# 001-0001_Christmas_Ornament_LEDs.net
KiCad netlist of a schematic drawn in Altium Designer
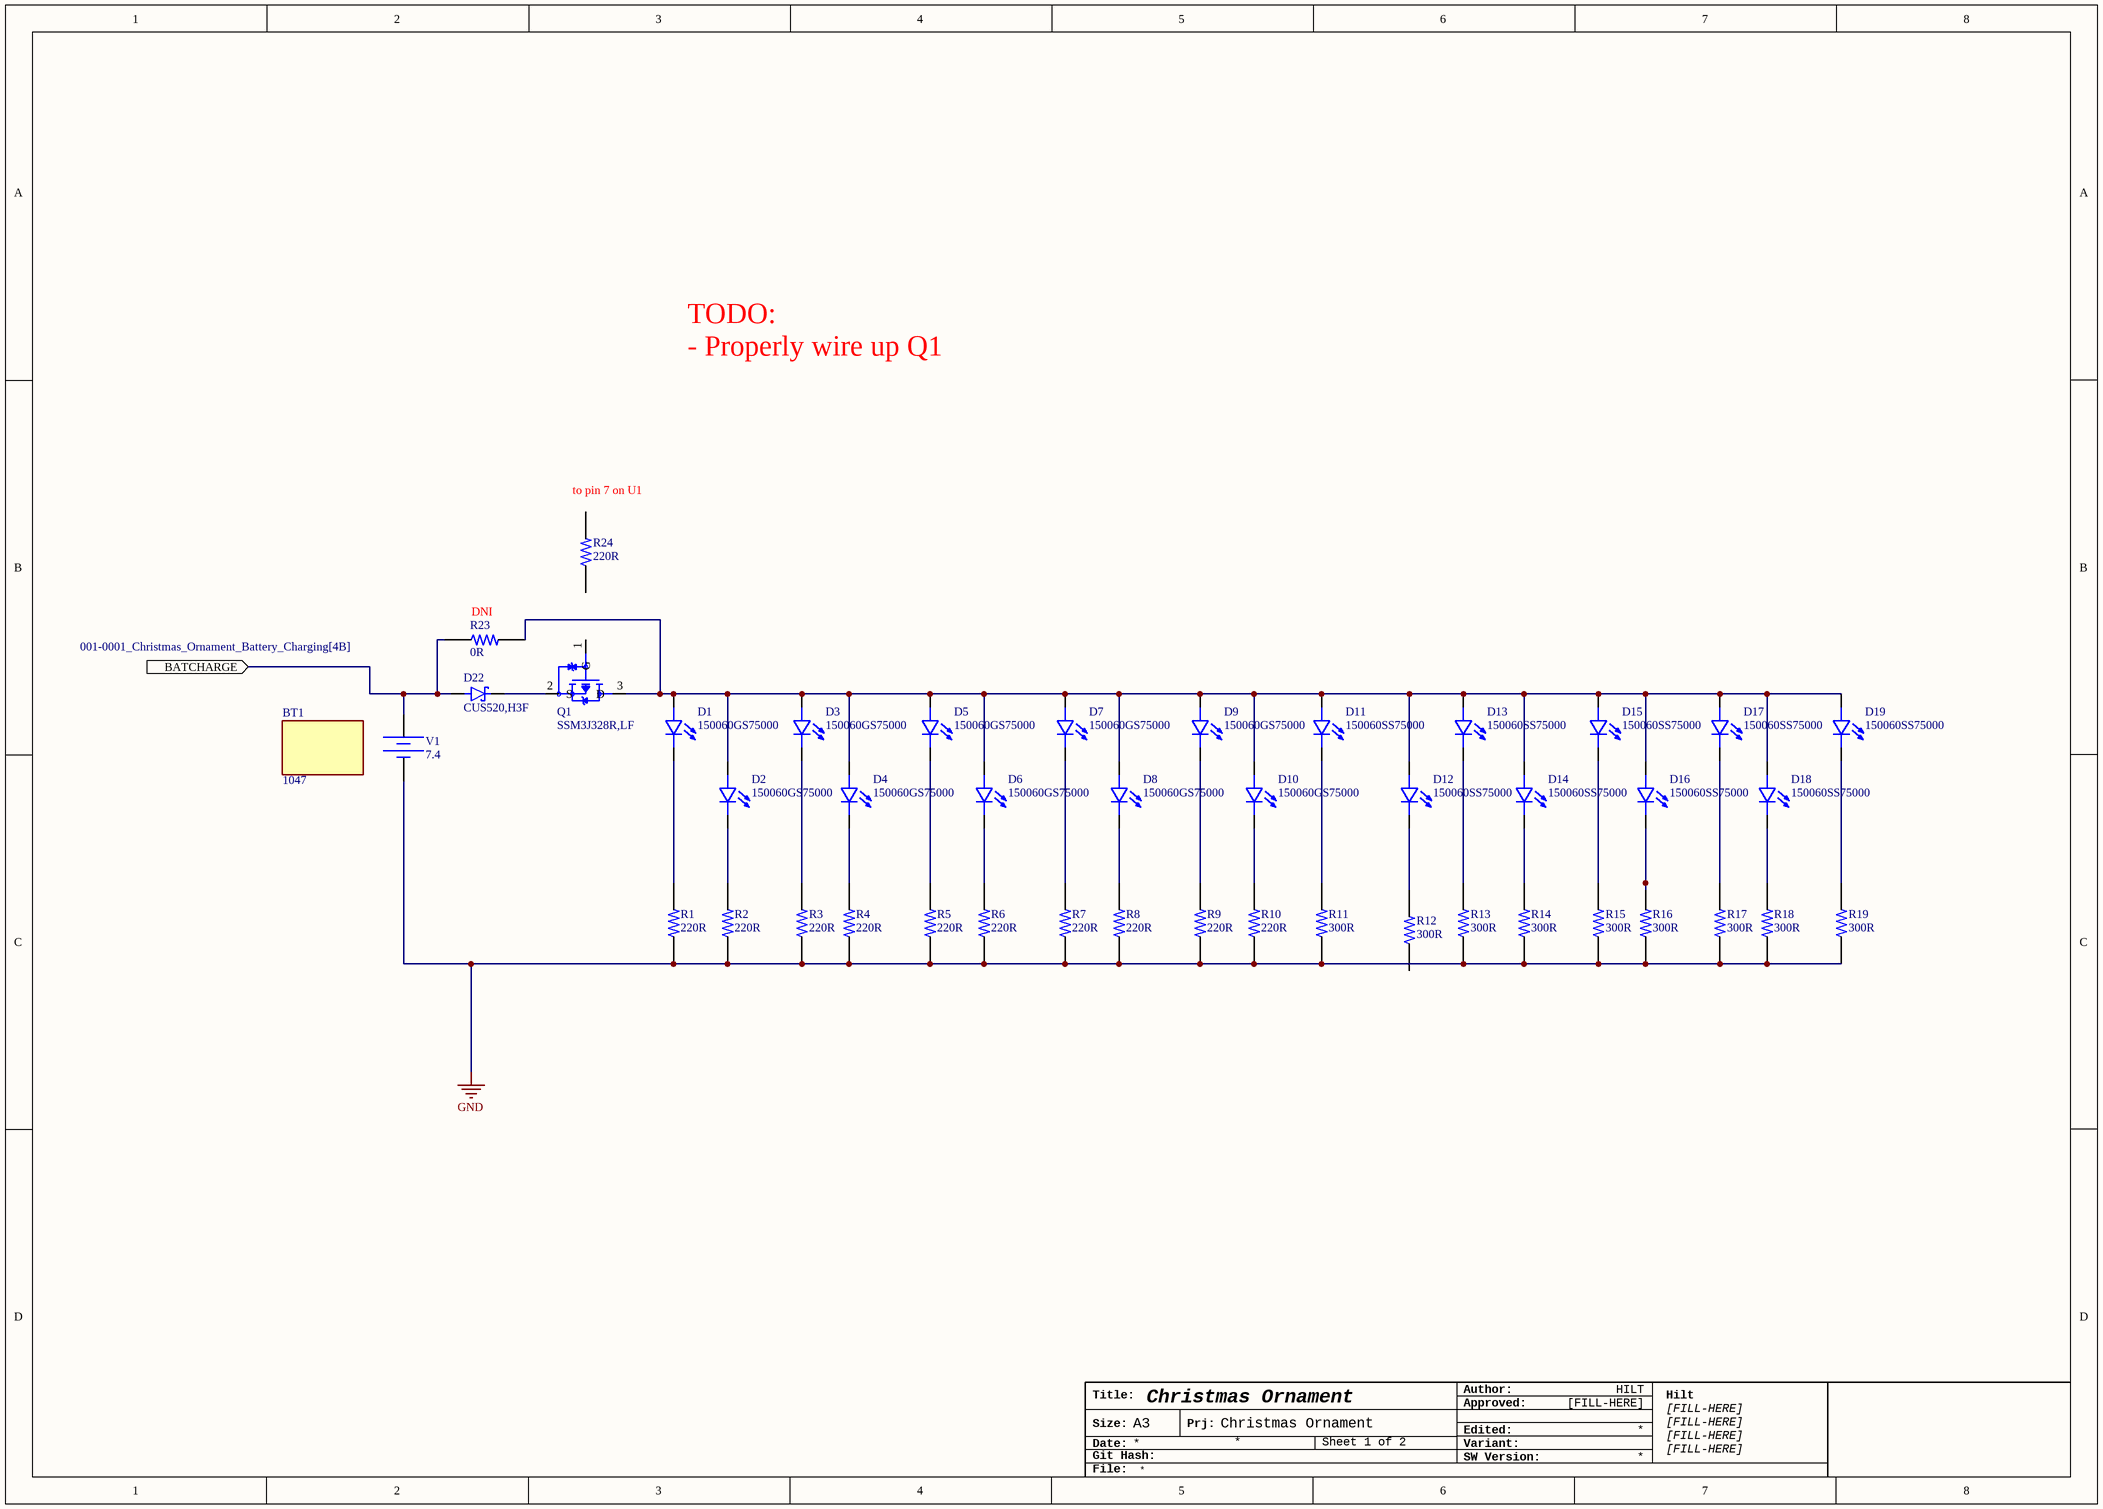
[diagram p0: 001-0001_Christmas_Ornament_LEDs.SchDoc]

(export (version "E")
  (design (tool "Eeschema 10.0.6"))
  (components
    (comp (ref "BT1")
      (value "1047")
      (footprint "BAT_1047")
      (description "18650 Dual Battery Holder")
      (libsource (lib "default") (part "1047"))
    )
    (comp (ref "D1")
      (value "150060GS75000")
      (footprint "LEDC1608X80N")
      (description "Green 520nm LED Indication - Discrete 3.2V 0603 (1608 Metric)")
      (fields (field (name "MF") "Wurth Electronics"))
      (libsource (lib "default") (part "150060GS75000"))
    )
    (comp (ref "D2")
      (value "150060GS75000")
      (footprint "LEDC1608X80N")
      (description "Green 520nm LED Indication - Discrete 3.2V 0603 (1608 Metric)")
      (fields (field (name "MF") "Wurth Electronics"))
      (libsource (lib "default") (part "150060GS75000"))
    )
    (comp (ref "D3")
      (value "150060GS75000")
      (footprint "LEDC1608X80N")
      (description "Green 520nm LED Indication - Discrete 3.2V 0603 (1608 Metric)")
      (fields (field (name "MF") "Wurth Electronics"))
      (libsource (lib "default") (part "150060GS75000"))
    )
    (comp (ref "D4")
      (value "150060GS75000")
      (footprint "LEDC1608X80N")
      (description "Green 520nm LED Indication - Discrete 3.2V 0603 (1608 Metric)")
      (fields (field (name "MF") "Wurth Electronics"))
      (libsource (lib "default") (part "150060GS75000"))
    )
    (comp (ref "D5")
      (value "150060GS75000")
      (footprint "LEDC1608X80N")
      (description "Green 520nm LED Indication - Discrete 3.2V 0603 (1608 Metric)")
      (fields (field (name "MF") "Wurth Electronics"))
      (libsource (lib "default") (part "150060GS75000"))
    )
    (comp (ref "D6")
      (value "150060GS75000")
      (footprint "LEDC1608X80N")
      (description "Green 520nm LED Indication - Discrete 3.2V 0603 (1608 Metric)")
      (fields (field (name "MF") "Wurth Electronics"))
      (libsource (lib "default") (part "150060GS75000"))
    )
    (comp (ref "D7")
      (value "150060GS75000")
      (footprint "LEDC1608X80N")
      (description "Green 520nm LED Indication - Discrete 3.2V 0603 (1608 Metric)")
      (fields (field (name "MF") "Wurth Electronics"))
      (libsource (lib "default") (part "150060GS75000"))
    )
    (comp (ref "D8")
      (value "150060GS75000")
      (footprint "LEDC1608X80N")
      (description "Green 520nm LED Indication - Discrete 3.2V 0603 (1608 Metric)")
      (fields (field (name "MF") "Wurth Electronics"))
      (libsource (lib "default") (part "150060GS75000"))
    )
    (comp (ref "D9")
      (value "150060GS75000")
      (footprint "LEDC1608X80N")
      (description "Green 520nm LED Indication - Discrete 3.2V 0603 (1608 Metric)")
      (fields (field (name "MF") "Wurth Electronics"))
      (libsource (lib "default") (part "150060GS75000"))
    )
    (comp (ref "D10")
      (value "150060GS75000")
      (footprint "LEDC1608X80N")
      (description "Green 520nm LED Indication - Discrete 3.2V 0603 (1608 Metric)")
      (fields (field (name "MF") "Wurth Electronics"))
      (libsource (lib "default") (part "150060GS75000"))
    )
    (comp (ref "D11")
      (value "150060SS75000")
      (footprint "LED_150060SS75000")
      (fields (field (name "MF") "{'manufacturer': u'Wurth Electronics'}"))
      (libsource (lib "default") (part "150060SS75000"))
    )
    (comp (ref "D12")
      (value "150060SS75000")
      (footprint "LED_150060SS75000")
      (fields (field (name "MF") "{'manufacturer': u'Wurth Electronics'}"))
      (libsource (lib "default") (part "150060SS75000"))
    )
    (comp (ref "D13")
      (value "150060SS75000")
      (footprint "LED_150060SS75000")
      (fields (field (name "MF") "{'manufacturer': u'Wurth Electronics'}"))
      (libsource (lib "default") (part "150060SS75000"))
    )
    (comp (ref "D14")
      (value "150060SS75000")
      (footprint "LED_150060SS75000")
      (fields (field (name "MF") "{'manufacturer': u'Wurth Electronics'}"))
      (libsource (lib "default") (part "150060SS75000"))
    )
    (comp (ref "D15")
      (value "150060SS75000")
      (footprint "LED_150060SS75000")
      (fields (field (name "MF") "{'manufacturer': u'Wurth Electronics'}"))
      (libsource (lib "default") (part "150060SS75000"))
    )
    (comp (ref "D16")
      (value "150060SS75000")
      (footprint "LED_150060SS75000")
      (fields (field (name "MF") "{'manufacturer': u'Wurth Electronics'}"))
      (libsource (lib "default") (part "150060SS75000"))
    )
    (comp (ref "D17")
      (value "150060SS75000")
      (footprint "LED_150060SS75000")
      (fields (field (name "MF") "{'manufacturer': u'Wurth Electronics'}"))
      (libsource (lib "default") (part "150060SS75000"))
    )
    (comp (ref "D18")
      (value "150060SS75000")
      (footprint "LED_150060SS75000")
      (fields (field (name "MF") "{'manufacturer': u'Wurth Electronics'}"))
      (libsource (lib "default") (part "150060SS75000"))
    )
    (comp (ref "D19")
      (value "150060SS75000")
      (footprint "LED_150060SS75000")
      (fields (field (name "MF") "{'manufacturer': u'Wurth Electronics'}"))
      (libsource (lib "default") (part "150060SS75000"))
    )
    (comp (ref "D22")
      (value "CUS520,H3F")
      (footprint "CUS520,H3F")
      (description "Diode Schottky 30V 200mA Surface Mount USC")
      (fields (field (name "MF") "Toshiba Semiconductor"))
      (libsource (lib "default") (part "CUS520,H3F"))
    )
    (comp (ref "Q1")
      (value "SSM3J328R,LF")
      (footprint "SSM3J328R,LF")
      (description "P-Channel 20V 6A _Ta_ 1W _Ta_ Surface Mount SOT-23F")
      (fields (field (name "MF") "Toshiba"))
      (libsource (lib "default") (part "SSM3J328R,LF"))
    )
    (comp (ref "R1")
      (value "220R")
      (footprint "default:ERJ-PA3F51R0V")
      (description "RES SMD 220 OHM 1% 1/3W 0603")
      (fields (field (name "MP") "ERJPA3F51R0V"))
      (libsource (lib "default") (part "ERJ-PA3F2200V"))
    )
    (comp (ref "R2")
      (value "220R")
      (footprint "default:ERJ-PA3F51R0V")
      (description "RES SMD 220 OHM 1% 1/3W 0603")
      (fields (field (name "MP") "ERJPA3F51R0V"))
      (libsource (lib "default") (part "ERJ-PA3F2200V"))
    )
    (comp (ref "R3")
      (value "220R")
      (footprint "default:ERJ-PA3F51R0V")
      (description "RES SMD 220 OHM 1% 1/3W 0603")
      (fields (field (name "MP") "ERJPA3F51R0V"))
      (libsource (lib "default") (part "ERJ-PA3F2200V"))
    )
    (comp (ref "R4")
      (value "220R")
      (footprint "default:ERJ-PA3F51R0V")
      (description "RES SMD 220 OHM 1% 1/3W 0603")
      (fields (field (name "MP") "ERJPA3F51R0V"))
      (libsource (lib "default") (part "ERJ-PA3F2200V"))
    )
    (comp (ref "R5")
      (value "220R")
      (footprint "default:ERJ-PA3F51R0V")
      (description "RES SMD 220 OHM 1% 1/3W 0603")
      (fields (field (name "MP") "ERJPA3F51R0V"))
      (libsource (lib "default") (part "ERJ-PA3F2200V"))
    )
    (comp (ref "R6")
      (value "220R")
      (footprint "default:ERJ-PA3F51R0V")
      (description "RES SMD 220 OHM 1% 1/3W 0603")
      (fields (field (name "MP") "ERJPA3F51R0V"))
      (libsource (lib "default") (part "ERJ-PA3F2200V"))
    )
    (comp (ref "R7")
      (value "220R")
      (footprint "default:ERJ-PA3F51R0V")
      (description "RES SMD 220 OHM 1% 1/3W 0603")
      (fields (field (name "MP") "ERJPA3F51R0V"))
      (libsource (lib "default") (part "ERJ-PA3F2200V"))
    )
    (comp (ref "R8")
      (value "220R")
      (footprint "default:ERJ-PA3F51R0V")
      (description "RES SMD 220 OHM 1% 1/3W 0603")
      (fields (field (name "MP") "ERJPA3F51R0V"))
      (libsource (lib "default") (part "ERJ-PA3F2200V"))
    )
    (comp (ref "R9")
      (value "220R")
      (footprint "default:ERJ-PA3F51R0V")
      (description "RES SMD 220 OHM 1% 1/3W 0603")
      (fields (field (name "MP") "ERJPA3F51R0V"))
      (libsource (lib "default") (part "ERJ-PA3F2200V"))
    )
    (comp (ref "R10")
      (value "220R")
      (footprint "default:ERJ-PA3F51R0V")
      (description "RES SMD 220 OHM 1% 1/3W 0603")
      (fields (field (name "MP") "ERJPA3F51R0V"))
      (libsource (lib "default") (part "ERJ-PA3F2200V"))
    )
    (comp (ref "R11")
      (value "300R")
      (footprint "default:ERJ-PA3F51R0V")
      (description "RES SMD 300 OHM 1% 1/3W 0603")
      (fields (field (name "MP") "ERJPA3F51R0V"))
      (libsource (lib "default") (part "ERJ-PA3F3000V"))
    )
    (comp (ref "R12")
      (value "300R")
      (footprint "default:ERJ-PA3F51R0V")
      (description "RES SMD 300 OHM 1% 1/3W 0603")
      (fields (field (name "MP") "ERJPA3F51R0V"))
      (libsource (lib "default") (part "ERJ-PA3F3000V"))
    )
    (comp (ref "R13")
      (value "300R")
      (footprint "default:ERJ-PA3F51R0V")
      (description "RES SMD 300 OHM 1% 1/3W 0603")
      (fields (field (name "MP") "ERJPA3F51R0V"))
      (libsource (lib "default") (part "ERJ-PA3F3000V"))
    )
    (comp (ref "R14")
      (value "300R")
      (footprint "default:ERJ-PA3F51R0V")
      (description "RES SMD 300 OHM 1% 1/3W 0603")
      (fields (field (name "MP") "ERJPA3F51R0V"))
      (libsource (lib "default") (part "ERJ-PA3F3000V"))
    )
    (comp (ref "R15")
      (value "300R")
      (footprint "default:ERJ-PA3F51R0V")
      (description "RES SMD 300 OHM 1% 1/3W 0603")
      (fields (field (name "MP") "ERJPA3F51R0V"))
      (libsource (lib "default") (part "ERJ-PA3F3000V"))
    )
    (comp (ref "R16")
      (value "300R")
      (footprint "default:ERJ-PA3F51R0V")
      (description "RES SMD 300 OHM 1% 1/3W 0603")
      (fields (field (name "MP") "ERJPA3F51R0V"))
      (libsource (lib "default") (part "ERJ-PA3F3000V"))
    )
    (comp (ref "R17")
      (value "300R")
      (footprint "default:ERJ-PA3F51R0V")
      (description "RES SMD 300 OHM 1% 1/3W 0603")
      (fields (field (name "MP") "ERJPA3F51R0V"))
      (libsource (lib "default") (part "ERJ-PA3F3000V"))
    )
    (comp (ref "R18")
      (value "300R")
      (footprint "default:ERJ-PA3F51R0V")
      (description "RES SMD 300 OHM 1% 1/3W 0603")
      (fields (field (name "MP") "ERJPA3F51R0V"))
      (libsource (lib "default") (part "ERJ-PA3F3000V"))
    )
    (comp (ref "R19")
      (value "300R")
      (footprint "default:ERJ-PA3F51R0V")
      (description "RES SMD 300 OHM 1% 1/3W 0603")
      (fields (field (name "MP") "ERJPA3F51R0V"))
      (libsource (lib "default") (part "ERJ-PA3F3000V"))
    )
    (comp (ref "R23")
      (value "0R")
      (footprint "default:ERJ-PA3F51R0V")
      (description "RES SMD 0 OHM JUMPER 1/10W 0603")
      (fields (field (name "MP") "ERJPA3F51R0V"))
      (libsource (lib "default") (part "ERJ-3GEY0R00V"))
    )
    (comp (ref "R24")
      (value "220R")
      (footprint "default:ERJ-PA3F51R0V")
      (description "RES SMD 10K OHM 1% 1/10W 0603")
      (fields (field (name "MP") "ERJPA3F51R0V"))
      (libsource (lib "default") (part "ERJ-3EKF1002V"))
    )
    (comp (ref "V1")
      (value "Constant Voltage Source")
      (fields (field (name "DC MAGNITUDE") "7.4"))
      (libsource (lib "Simulation Generic Components") (part "Battery"))
    )
  )
  (nets
    (net (code "1") (name "/BATCHARGE") (class "Default")
      (node (ref "D22") (pin "A") (pinfunction "A_A") (pintype "passive"))
      (node (ref "R23") (pin "1") (pinfunction "1_1") (pintype "passive"))
      (node (ref "V1") (pin "1") (pinfunction "1_1") (pintype "passive"))
    )
    (net (code "2") (name "GND") (class "Default")
      (node (ref "R1") (pin "1") (pinfunction "1_1") (pintype "passive"))
      (node (ref "R10") (pin "1") (pinfunction "1_1") (pintype "passive"))
      (node (ref "R11") (pin "1") (pinfunction "1_1") (pintype "passive"))
      (node (ref "R13") (pin "1") (pinfunction "1_1") (pintype "passive"))
      (node (ref "R14") (pin "1") (pinfunction "1_1") (pintype "passive"))
      (node (ref "R15") (pin "1") (pinfunction "1_1") (pintype "passive"))
      (node (ref "R16") (pin "1") (pinfunction "1_1") (pintype "passive"))
      (node (ref "R17") (pin "1") (pinfunction "1_1") (pintype "passive"))
      (node (ref "R18") (pin "1") (pinfunction "1_1") (pintype "passive"))
      (node (ref "R19") (pin "1") (pinfunction "1_1") (pintype "passive"))
      (node (ref "R2") (pin "1") (pinfunction "1_1") (pintype "passive"))
      (node (ref "R3") (pin "1") (pinfunction "1_1") (pintype "passive"))
      (node (ref "R4") (pin "1") (pinfunction "1_1") (pintype "passive"))
      (node (ref "R5") (pin "1") (pinfunction "1_1") (pintype "passive"))
      (node (ref "R6") (pin "1") (pinfunction "1_1") (pintype "passive"))
      (node (ref "R7") (pin "1") (pinfunction "1_1") (pintype "passive"))
      (node (ref "R8") (pin "1") (pinfunction "1_1") (pintype "passive"))
      (node (ref "R9") (pin "1") (pinfunction "1_1") (pintype "passive"))
      (node (ref "V1") (pin "2") (pinfunction "2_2") (pintype "passive"))
    )
    (net (code "3") (name "Net-(D1-PadC)") (class "Default")
      (node (ref "D1") (pin "C") (pinfunction "C_C") (pintype "passive"))
      (node (ref "R1") (pin "2") (pinfunction "2_2") (pintype "passive"))
    )
    (net (code "4") (name "Net-(D2-PadC)") (class "Default")
      (node (ref "D2") (pin "C") (pinfunction "C_C") (pintype "passive"))
      (node (ref "R2") (pin "2") (pinfunction "2_2") (pintype "passive"))
    )
    (net (code "5") (name "Net-(D3-PadC)") (class "Default")
      (node (ref "D3") (pin "C") (pinfunction "C_C") (pintype "passive"))
      (node (ref "R3") (pin "2") (pinfunction "2_2") (pintype "passive"))
    )
    (net (code "6") (name "Net-(D4-PadC)") (class "Default")
      (node (ref "D4") (pin "C") (pinfunction "C_C") (pintype "passive"))
      (node (ref "R4") (pin "2") (pinfunction "2_2") (pintype "passive"))
    )
    (net (code "7") (name "Net-(D5-PadC)") (class "Default")
      (node (ref "D5") (pin "C") (pinfunction "C_C") (pintype "passive"))
      (node (ref "R5") (pin "2") (pinfunction "2_2") (pintype "passive"))
    )
    (net (code "8") (name "Net-(D6-PadC)") (class "Default")
      (node (ref "D6") (pin "C") (pinfunction "C_C") (pintype "passive"))
      (node (ref "R6") (pin "2") (pinfunction "2_2") (pintype "passive"))
    )
    (net (code "9") (name "Net-(D7-PadC)") (class "Default")
      (node (ref "D7") (pin "C") (pinfunction "C_C") (pintype "passive"))
      (node (ref "R7") (pin "2") (pinfunction "2_2") (pintype "passive"))
    )
    (net (code "10") (name "Net-(D8-PadC)") (class "Default")
      (node (ref "D8") (pin "C") (pinfunction "C_C") (pintype "passive"))
      (node (ref "R8") (pin "2") (pinfunction "2_2") (pintype "passive"))
    )
    (net (code "11") (name "Net-(D9-PadC)") (class "Default")
      (node (ref "D9") (pin "C") (pinfunction "C_C") (pintype "passive"))
      (node (ref "R9") (pin "2") (pinfunction "2_2") (pintype "passive"))
    )
    (net (code "12") (name "Net-(D10-PadC)") (class "Default")
      (node (ref "D10") (pin "C") (pinfunction "C_C") (pintype "passive"))
      (node (ref "R10") (pin "2") (pinfunction "2_2") (pintype "passive"))
    )
    (net (code "13") (name "Net-(D11-PadC)") (class "Default")
      (node (ref "D11") (pin "C") (pinfunction "C_C") (pintype "passive"))
      (node (ref "R11") (pin "2") (pinfunction "2_2") (pintype "passive"))
    )
    (net (code "14") (name "Net-(D12-PadC)") (class "Default")
      (node (ref "D12") (pin "C") (pinfunction "C_C") (pintype "passive"))
      (node (ref "R12") (pin "2") (pinfunction "2_2") (pintype "passive"))
    )
    (net (code "15") (name "Net-(D13-PadC)") (class "Default")
      (node (ref "D13") (pin "C") (pinfunction "C_C") (pintype "passive"))
      (node (ref "R13") (pin "2") (pinfunction "2_2") (pintype "passive"))
    )
    (net (code "16") (name "Net-(D14-PadC)") (class "Default")
      (node (ref "D14") (pin "C") (pinfunction "C_C") (pintype "passive"))
      (node (ref "R14") (pin "2") (pinfunction "2_2") (pintype "passive"))
    )
    (net (code "17") (name "Net-(D15-PadC)") (class "Default")
      (node (ref "D15") (pin "C") (pinfunction "C_C") (pintype "passive"))
      (node (ref "R15") (pin "2") (pinfunction "2_2") (pintype "passive"))
    )
    (net (code "18") (name "Net-(D16-PadC)") (class "Default")
      (node (ref "D16") (pin "C") (pinfunction "C_C") (pintype "passive"))
      (node (ref "R16") (pin "2") (pinfunction "2_2") (pintype "passive"))
    )
    (net (code "19") (name "Net-(D17-PadC)") (class "Default")
      (node (ref "D17") (pin "C") (pinfunction "C_C") (pintype "passive"))
      (node (ref "R17") (pin "2") (pinfunction "2_2") (pintype "passive"))
    )
    (net (code "20") (name "Net-(D18-PadC)") (class "Default")
      (node (ref "D18") (pin "C") (pinfunction "C_C") (pintype "passive"))
      (node (ref "R18") (pin "2") (pinfunction "2_2") (pintype "passive"))
    )
    (net (code "21") (name "Net-(D19-PadC)") (class "Default")
      (node (ref "D19") (pin "C") (pinfunction "C_C") (pintype "passive"))
      (node (ref "R19") (pin "2") (pinfunction "2_2") (pintype "passive"))
    )
    (net (code "22") (name "Net-(Q1-D)") (class "Default")
      (node (ref "D1") (pin "A") (pinfunction "A_A") (pintype "passive"))
      (node (ref "D10") (pin "A") (pinfunction "A_A") (pintype "passive"))
      (node (ref "D11") (pin "A") (pinfunction "A_A") (pintype "passive"))
      (node (ref "D12") (pin "A") (pinfunction "A_A") (pintype "passive"))
      (node (ref "D13") (pin "A") (pinfunction "A_A") (pintype "passive"))
      (node (ref "D14") (pin "A") (pinfunction "A_A") (pintype "passive"))
      (node (ref "D15") (pin "A") (pinfunction "A_A") (pintype "passive"))
      (node (ref "D16") (pin "A") (pinfunction "A_A") (pintype "passive"))
      (node (ref "D17") (pin "A") (pinfunction "A_A") (pintype "passive"))
      (node (ref "D18") (pin "A") (pinfunction "A_A") (pintype "passive"))
      (node (ref "D19") (pin "A") (pinfunction "A_A") (pintype "passive"))
      (node (ref "D2") (pin "A") (pinfunction "A_A") (pintype "passive"))
      (node (ref "D3") (pin "A") (pinfunction "A_A") (pintype "passive"))
      (node (ref "D4") (pin "A") (pinfunction "A_A") (pintype "passive"))
      (node (ref "D5") (pin "A") (pinfunction "A_A") (pintype "passive"))
      (node (ref "D6") (pin "A") (pinfunction "A_A") (pintype "passive"))
      (node (ref "D7") (pin "A") (pinfunction "A_A") (pintype "passive"))
      (node (ref "D8") (pin "A") (pinfunction "A_A") (pintype "passive"))
      (node (ref "D9") (pin "A") (pinfunction "A_A") (pintype "passive"))
      (node (ref "Q1") (pin "3") (pinfunction "D_3") (pintype "passive"))
      (node (ref "R23") (pin "2") (pinfunction "2_2") (pintype "passive"))
    )
    (net (code "23") (name "Net-(Q1-S)") (class "Default")
      (node (ref "D22") (pin "C") (pinfunction "C_C") (pintype "passive"))
      (node (ref "Q1") (pin "2") (pinfunction "S_2") (pintype "passive"))
    )
    (net (code "24") (name "unconnected-(Q1-G-Pad1)") (class "Default")
      (node (ref "Q1") (pin "1") (pinfunction "G_1") (pintype "passive"))
    )
    (net (code "25") (name "unconnected-(R12-Pad1)") (class "Default")
      (node (ref "R12") (pin "1") (pinfunction "1_1") (pintype "passive"))
    )
    (net (code "26") (name "unconnected-(R24-Pad1)") (class "Default")
      (node (ref "R24") (pin "1") (pinfunction "1_1") (pintype "passive"))
    )
    (net (code "27") (name "unconnected-(R24-Pad2)") (class "Default")
      (node (ref "R24") (pin "2") (pinfunction "2_2") (pintype "passive"))
    )
  )
)
